# SENSORS.net
KiCad netlist of a schematic drawn in Altium Designer
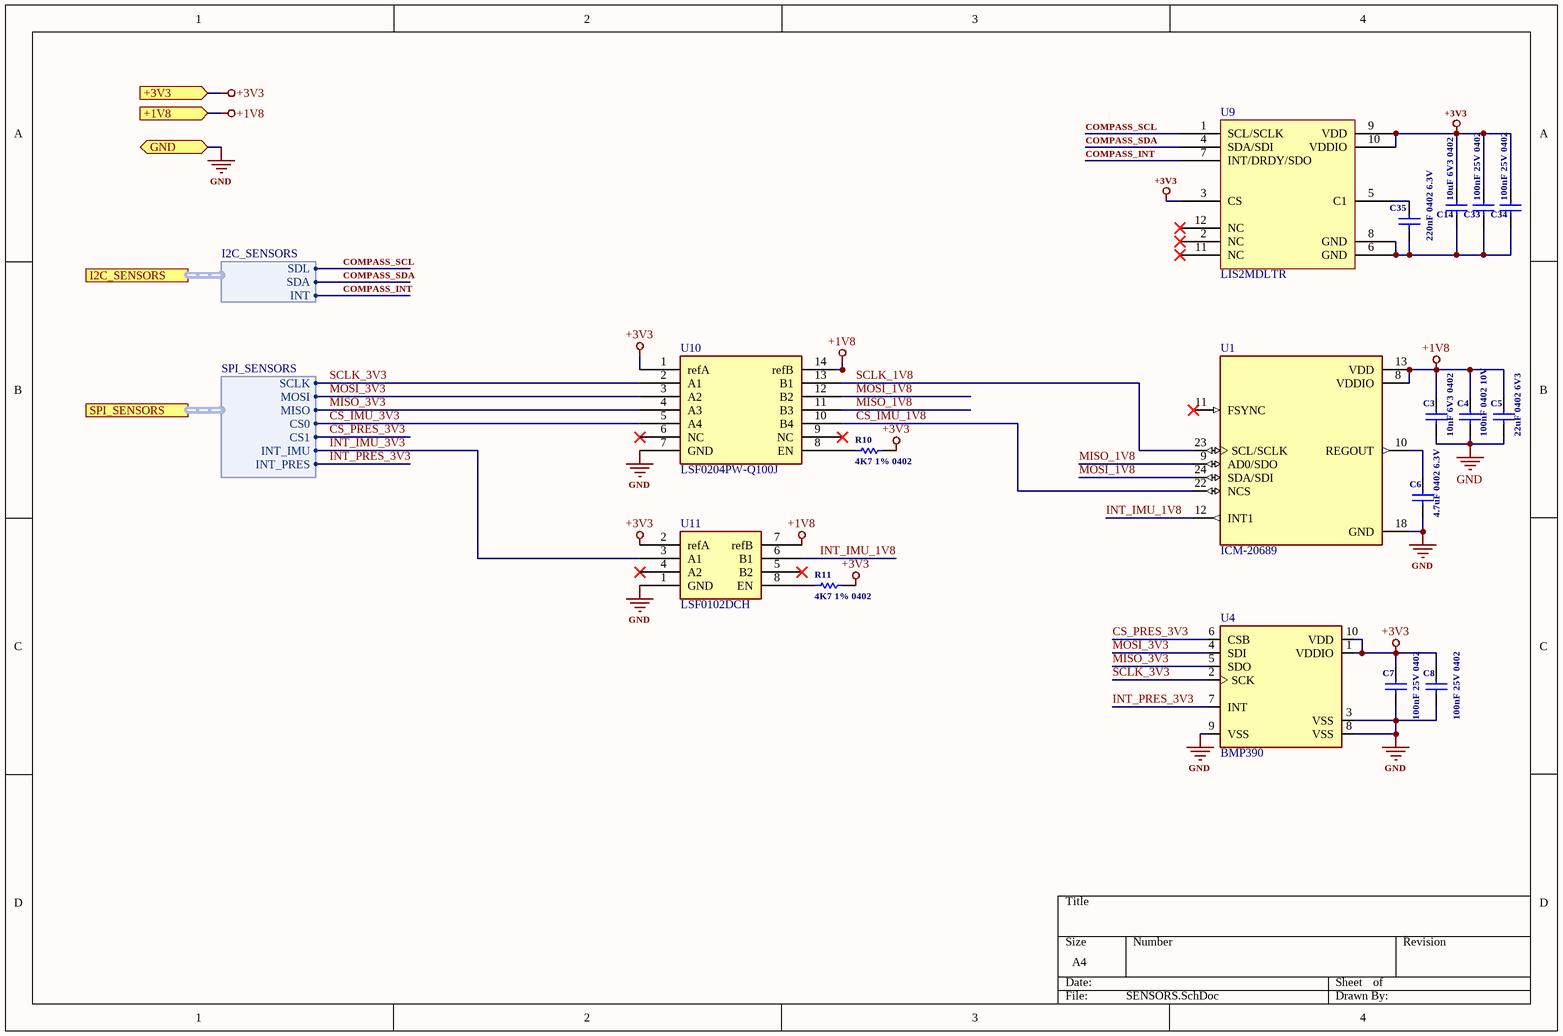
[diagram p0: SENSORS.SchDoc]

(export (version "E")
  (design (tool "Eeschema 10.0.6"))
  (components
    (comp (ref "C3")
      (value "10nF 6V3 0402")
      (description "04026C103KAT2A  10nF 6.3V")
      (libsource (lib "CondensadoresGenericos") (part "04026C103KAT2A  10nF 6.3V"))
    )
    (comp (ref "C4")
      (value "100nF 0402 10V")
      (description "Cap Ceramic 0.1uF 10V X5R 10% SMD 0402 85C Paper T/R")
      (fields
        (field (name "MANUFACTURER") "Samsung")
        (field (name "MANUFACTURER PART NUMBER") "CL05A104KP5NNNC")
      )
      (libsource (lib "CondensadoresGenericos") (part "CL05A104KP5NNNC 100nF 0402 10V"))
    )
    (comp (ref "C5")
      (value "22uF 0402 6V3")
      (description "CL05 Series 22 uF 6.3 V ±20% Tolerance X5R SMT Multilayer Ceramic Capacitor")
      (fields
        (field (name "MANUFACTURER") "Samsung")
        (field (name "MANUFACTURER PART NUMBER") "CL05A226MQ5N6J8")
      )
      (libsource (lib "CondensadoresGenericos") (part "CL05A226MQ5N6J8 22uF 0402 6V3"))
    )
    (comp (ref "C6")
      (value "4.7uF 0402 6.3V")
      (fields
        (field (name "MANUFACTURER") "Murata")
        (field (name "MANUFACTURER PART NUMBER") "GRM155R60J475ME87D")
        (field (name "VOLTAGE") "6.3 Vdc")
      )
      (libsource (lib "CondensadoresGenericos") (part "GRM155R60J475ME87D 4.7uF 0402 6.3V"))
    )
    (comp (ref "C7")
      (value "100nF 25V 0402")
      (description "100nF, 25V, MLCC, 0402")
      (fields
        (field (name "MANUFACTURER") "Samsung")
        (field (name "MANUFACTURER PART NUMBER") "CL05A104KA5NNNC")
      )
      (libsource (lib "CondensadoresGenericos") (part "CL05A104KA5NNNC 100nf 0402"))
    )
    (comp (ref "C8")
      (value "100nF 25V 0402")
      (description "100nF, 25V, MLCC, 0402")
      (fields
        (field (name "MANUFACTURER") "Samsung")
        (field (name "MANUFACTURER PART NUMBER") "CL05A104KA5NNNC")
      )
      (libsource (lib "CondensadoresGenericos") (part "CL05A104KA5NNNC 100nf 0402"))
    )
    (comp (ref "C14")
      (value "10uF 6V3 0402")
      (description "CL05A106MP5NUNC CAP CER 10UF 10V X5R 0402")
      (libsource (lib "CondensadoresGenericos") (part "CL05A106MP5NUNC 10uF 0402"))
    )
    (comp (ref "C33")
      (value "100nF 25V 0402")
      (description "100nF, 25V, MLCC, 0402")
      (fields
        (field (name "MANUFACTURER") "Samsung")
        (field (name "MANUFACTURER PART NUMBER") "CL05A104KA5NNNC")
      )
      (libsource (lib "CondensadoresGenericos") (part "CL05A104KA5NNNC 100nf 0402"))
    )
    (comp (ref "C34")
      (value "100nF 25V 0402")
      (description "100nF, 25V, MLCC, 0402")
      (fields
        (field (name "MANUFACTURER") "Samsung")
        (field (name "MANUFACTURER PART NUMBER") "CL05A104KA5NNNC")
      )
      (libsource (lib "CondensadoresGenericos") (part "CL05A104KA5NNNC 100nf 0402"))
    )
    (comp (ref "C35")
      (value "220nF 0402 6.3V")
      (fields
        (field (name "MANUFACTURER") "Samsung")
        (field (name "MANUFACTURER PART NUMBER") "CL05B224KO5NNNC")
      )
      (libsource (lib "CondensadoresGenericos") (part "CL05B224KO5NNNC 220nF 0402 6.3V"))
    )
    (comp (ref "R10")
      (value "4K7 1% 0402")
      (footprint "Resistor_0402")
      (description "Thick Film Resistors 1/16W 4.7K ohm 1% AEC-Q200")
      (fields
        (field (name "MANUFACTURER") "Yageo")
        (field (name "MANUFACTURER PART NUMBER") "AC0402FR-074K7L")
      )
      (libsource (lib "ResistenciasGenericas") (part "AC0402FR-074K7L 4.7K 1% 0402"))
    )
    (comp (ref "R11")
      (value "4K7 1% 0402")
      (footprint "Resistor_0402")
      (description "Thick Film Resistors 1/16W 4.7K ohm 1% AEC-Q200")
      (fields
        (field (name "MANUFACTURER") "Yageo")
        (field (name "MANUFACTURER PART NUMBER") "AC0402FR-074K7L")
      )
      (libsource (lib "ResistenciasGenericas") (part "AC0402FR-074K7L 4.7K 1% 0402"))
    )
    (comp (ref "U1")
      (value "ICM-20689")
      (description "IMU ACCEL/GYRO/COMPI2C/SPI 24QFN")
      (libsource (lib "TDK_InvenSense") (part "ICM-20689"))
    )
    (comp (ref "U4") (value "BMP390") (libsource (lib "Bosch") (part "BMP390")))
    (comp (ref "U9") (value "LIS2MDLTR") (libsource (lib "STM_Sensors") (part "LIS2MDLTR")))
    (comp (ref "U10")
      (value "LSF0204PW-Q100J")
      (footprint "TSOP65P640X110-14N")
      (description "Nivel de voltaje Traductores Bidireccional 1 circuitos 4 canales 120MHz 14-TSSOP")
      (libsource (lib "LevelConversors") (part "LSF0204PW-Q100J"))
    )
    (comp (ref "U11")
      (value "LSF0102DCH")
      (description "Voltage Level Translator Bidirectional 1 Circuit 2 Channel 100MHz 8-VSSOP")
      (libsource (lib "LevelConversors") (part "LSF0102DCH"))
    )
  )
  (nets
    (net (code "3") (name "+1V8") (class "Default")
      (node (ref "C3") (pin "2") (pinfunction "2_2") (pintype "passive"))
      (node (ref "C4") (pin "2") (pinfunction "2_2") (pintype "passive"))
      (node (ref "C5") (pin "2") (pinfunction "2_2") (pintype "passive"))
      (node (ref "U1") (pin "13") (pinfunction "VDD_13") (pintype "power_in"))
      (node (ref "U1") (pin "8") (pinfunction "VDDIO_8") (pintype "power_in"))
      (node (ref "U10") (pin "14") (pinfunction "refB_14") (pintype "passive"))
      (node (ref "U11") (pin "7") (pinfunction "refB_7") (pintype "passive"))
    )
    (net (code "4") (name "+3V3") (class "Default")
      (node (ref "C14") (pin "2") (pinfunction "2_2") (pintype "passive"))
      (node (ref "C33") (pin "2") (pinfunction "2_2") (pintype "passive"))
      (node (ref "C34") (pin "2") (pinfunction "2_2") (pintype "passive"))
      (node (ref "C7") (pin "2") (pinfunction "2_2") (pintype "passive"))
      (node (ref "C8") (pin "2") (pinfunction "2_2") (pintype "passive"))
      (node (ref "R10") (pin "2") (pinfunction "2_2") (pintype "passive"))
      (node (ref "R11") (pin "2") (pinfunction "2_2") (pintype "passive"))
      (node (ref "U10") (pin "1") (pinfunction "refA_1") (pintype "passive"))
      (node (ref "U11") (pin "2") (pinfunction "refA_2") (pintype "passive"))
      (node (ref "U4") (pin "1") (pinfunction "VDDIO_1") (pintype "power_in"))
      (node (ref "U4") (pin "10") (pinfunction "VDD_10") (pintype "power_in"))
      (node (ref "U9") (pin "10") (pinfunction "VDDIO_10") (pintype "passive"))
      (node (ref "U9") (pin "3") (pinfunction "CS_3") (pintype "passive"))
      (node (ref "U9") (pin "9") (pinfunction "VDD_9") (pintype "passive"))
    )
    (net (code "5") (name "/COMPASS_INT") (class "Default")
      (node (ref "U9") (pin "7") (pinfunction "INT/DRDY/SDO_7") (pintype "passive"))
    )
    (net (code "6") (name "/COMPASS_SCL") (class "Default")
      (node (ref "U9") (pin "1") (pinfunction "SCL/SCLK_1") (pintype "passive"))
    )
    (net (code "7") (name "/COMPASS_SDA") (class "Default")
      (node (ref "U9") (pin "4") (pinfunction "SDA/SDI_4") (pintype "passive"))
    )
    (net (code "8") (name "/CS_IMU_1V8") (class "Default")
      (node (ref "U1") (pin "22") (pinfunction "NCS_22") (pintype "bidirectional"))
      (node (ref "U10") (pin "10") (pinfunction "B4_10") (pintype "passive"))
    )
    (net (code "9") (name "/CS_IMU_3V3") (class "Default")
      (node (ref "U10") (pin "5") (pinfunction "A4_5") (pintype "passive"))
    )
    (net (code "10") (name "/CS_PRES_3V3") (class "Default")
      (node (ref "U4") (pin "6") (pinfunction "CSB_6") (pintype "bidirectional"))
    )
    (net (code "11") (name "/INT_IMU_1V8") (class "Default")
      (node (ref "U1") (pin "12") (pinfunction "INT1_12") (pintype "output"))
      (node (ref "U11") (pin "6") (pinfunction "B1_6") (pintype "passive"))
    )
    (net (code "12") (name "/INT_IMU_3V3") (class "Default")
      (node (ref "U11") (pin "3") (pinfunction "A1_3") (pintype "passive"))
    )
    (net (code "13") (name "/INT_PRES_3V3") (class "Default")
      (node (ref "U4") (pin "7") (pinfunction "INT_7") (pintype "passive"))
    )
    (net (code "14") (name "/MISO_1V8") (class "Default")
      (node (ref "U1") (pin "9") (pinfunction "AD0/SDO_9") (pintype "bidirectional"))
      (node (ref "U10") (pin "11") (pinfunction "B3_11") (pintype "passive"))
    )
    (net (code "15") (name "/MISO_3V3") (class "Default")
      (node (ref "U10") (pin "4") (pinfunction "A3_4") (pintype "passive"))
      (node (ref "U4") (pin "5") (pinfunction "SDO_5") (pintype "bidirectional"))
    )
    (net (code "16") (name "/MOSI_1V8") (class "Default")
      (node (ref "U1") (pin "24") (pinfunction "SDA/SDI_24") (pintype "bidirectional"))
      (node (ref "U10") (pin "12") (pinfunction "B2_12") (pintype "passive"))
    )
    (net (code "17") (name "/MOSI_3V3") (class "Default")
      (node (ref "U10") (pin "3") (pinfunction "A2_3") (pintype "passive"))
      (node (ref "U4") (pin "4") (pinfunction "SDI_4") (pintype "bidirectional"))
    )
    (net (code "18") (name "/SCLK_1V8") (class "Default")
      (node (ref "U1") (pin "23") (pinfunction "SCL/SCLK_23") (pintype "bidirectional"))
      (node (ref "U10") (pin "13") (pinfunction "B1_13") (pintype "passive"))
    )
    (net (code "19") (name "/SCLK_3V3") (class "Default")
      (node (ref "U10") (pin "2") (pinfunction "A1_2") (pintype "passive"))
      (node (ref "U4") (pin "2") (pinfunction "SCK_2") (pintype "bidirectional"))
    )
    (net (code "22") (name "GND") (class "Default")
      (node (ref "C3") (pin "1") (pinfunction "1_1") (pintype "passive"))
      (node (ref "C4") (pin "1") (pinfunction "1_1") (pintype "passive"))
      (node (ref "C5") (pin "1") (pinfunction "1_1") (pintype "passive"))
      (node (ref "C6") (pin "1") (pinfunction "1_1") (pintype "passive"))
      (node (ref "C7") (pin "1") (pinfunction "1_1") (pintype "passive"))
      (node (ref "C8") (pin "1") (pinfunction "1_1") (pintype "passive"))
      (node (ref "U1") (pin "18") (pinfunction "GND_18") (pintype "power_in"))
      (node (ref "U10") (pin "7") (pinfunction "GND_7") (pintype "passive"))
      (node (ref "U11") (pin "1") (pinfunction "GND_1") (pintype "passive"))
      (node (ref "U4") (pin "3") (pinfunction "VSS_3") (pintype "power_in"))
      (node (ref "U4") (pin "8") (pinfunction "VSS_8") (pintype "power_in"))
      (node (ref "U4") (pin "9") (pinfunction "VSS_9") (pintype "power_in"))
    )
    (net (code "23") (name "Net-(C14-Pad1)") (class "Default")
      (node (ref "C14") (pin "1") (pinfunction "1_1") (pintype "passive"))
      (node (ref "C33") (pin "1") (pinfunction "1_1") (pintype "passive"))
      (node (ref "C34") (pin "1") (pinfunction "1_1") (pintype "passive"))
      (node (ref "C35") (pin "2") (pinfunction "2_2") (pintype "passive"))
      (node (ref "U9") (pin "6") (pinfunction "GND_6") (pintype "passive"))
      (node (ref "U9") (pin "8") (pinfunction "GND_8") (pintype "passive"))
    )
    (net (code "24") (name "Net-(U1-REGOUT)") (class "Default")
      (node (ref "C6") (pin "2") (pinfunction "2_2") (pintype "passive"))
      (node (ref "U1") (pin "10") (pinfunction "REGOUT_10") (pintype "output"))
    )
    (net (code "25") (name "Net-(U9-C1)") (class "Default")
      (node (ref "C35") (pin "1") (pinfunction "1_1") (pintype "passive"))
      (node (ref "U9") (pin "5") (pinfunction "C1_5") (pintype "passive"))
    )
    (net (code "26") (name "Net-(U10-EN)") (class "Default")
      (node (ref "R10") (pin "1") (pinfunction "1_1") (pintype "passive"))
      (node (ref "U10") (pin "8") (pinfunction "EN_8") (pintype "passive"))
    )
    (net (code "27") (name "Net-(U11-EN)") (class "Default")
      (node (ref "R11") (pin "1") (pinfunction "1_1") (pintype "passive"))
      (node (ref "U11") (pin "8") (pinfunction "EN_8") (pintype "passive"))
    )
    (net (code "28") (name "unconnected-(U1-FSYNC-Pad11)") (class "Default")
      (node (ref "U1") (pin "11") (pinfunction "FSYNC_11") (pintype "input+no_connect"))
    )
    (net (code "29") (name "unconnected-(U9-NC-Pad2)") (class "Default")
      (node (ref "U9") (pin "2") (pinfunction "NC_2") (pintype "passive+no_connect"))
    )
    (net (code "30") (name "unconnected-(U9-NC-Pad11)") (class "Default")
      (node (ref "U9") (pin "11") (pinfunction "NC_11") (pintype "passive+no_connect"))
    )
    (net (code "31") (name "unconnected-(U9-NC-Pad12)") (class "Default")
      (node (ref "U9") (pin "12") (pinfunction "NC_12") (pintype "passive+no_connect"))
    )
    (net (code "32") (name "unconnected-(U10-NC-Pad6)") (class "Default")
      (node (ref "U10") (pin "6") (pinfunction "NC_6") (pintype "passive+no_connect"))
    )
    (net (code "33") (name "unconnected-(U10-NC-Pad9)") (class "Default")
      (node (ref "U10") (pin "9") (pinfunction "NC_9") (pintype "passive+no_connect"))
    )
    (net (code "34") (name "unconnected-(U11-A2-Pad4)") (class "Default")
      (node (ref "U11") (pin "4") (pinfunction "A2_4") (pintype "passive+no_connect"))
    )
    (net (code "35") (name "unconnected-(U11-B2-Pad5)") (class "Default")
      (node (ref "U11") (pin "5") (pinfunction "B2_5") (pintype "passive+no_connect"))
    )
  )
)
